# G1000_Pan_Range.net
KiCad netlist of a schematic drawn in EasyEDA
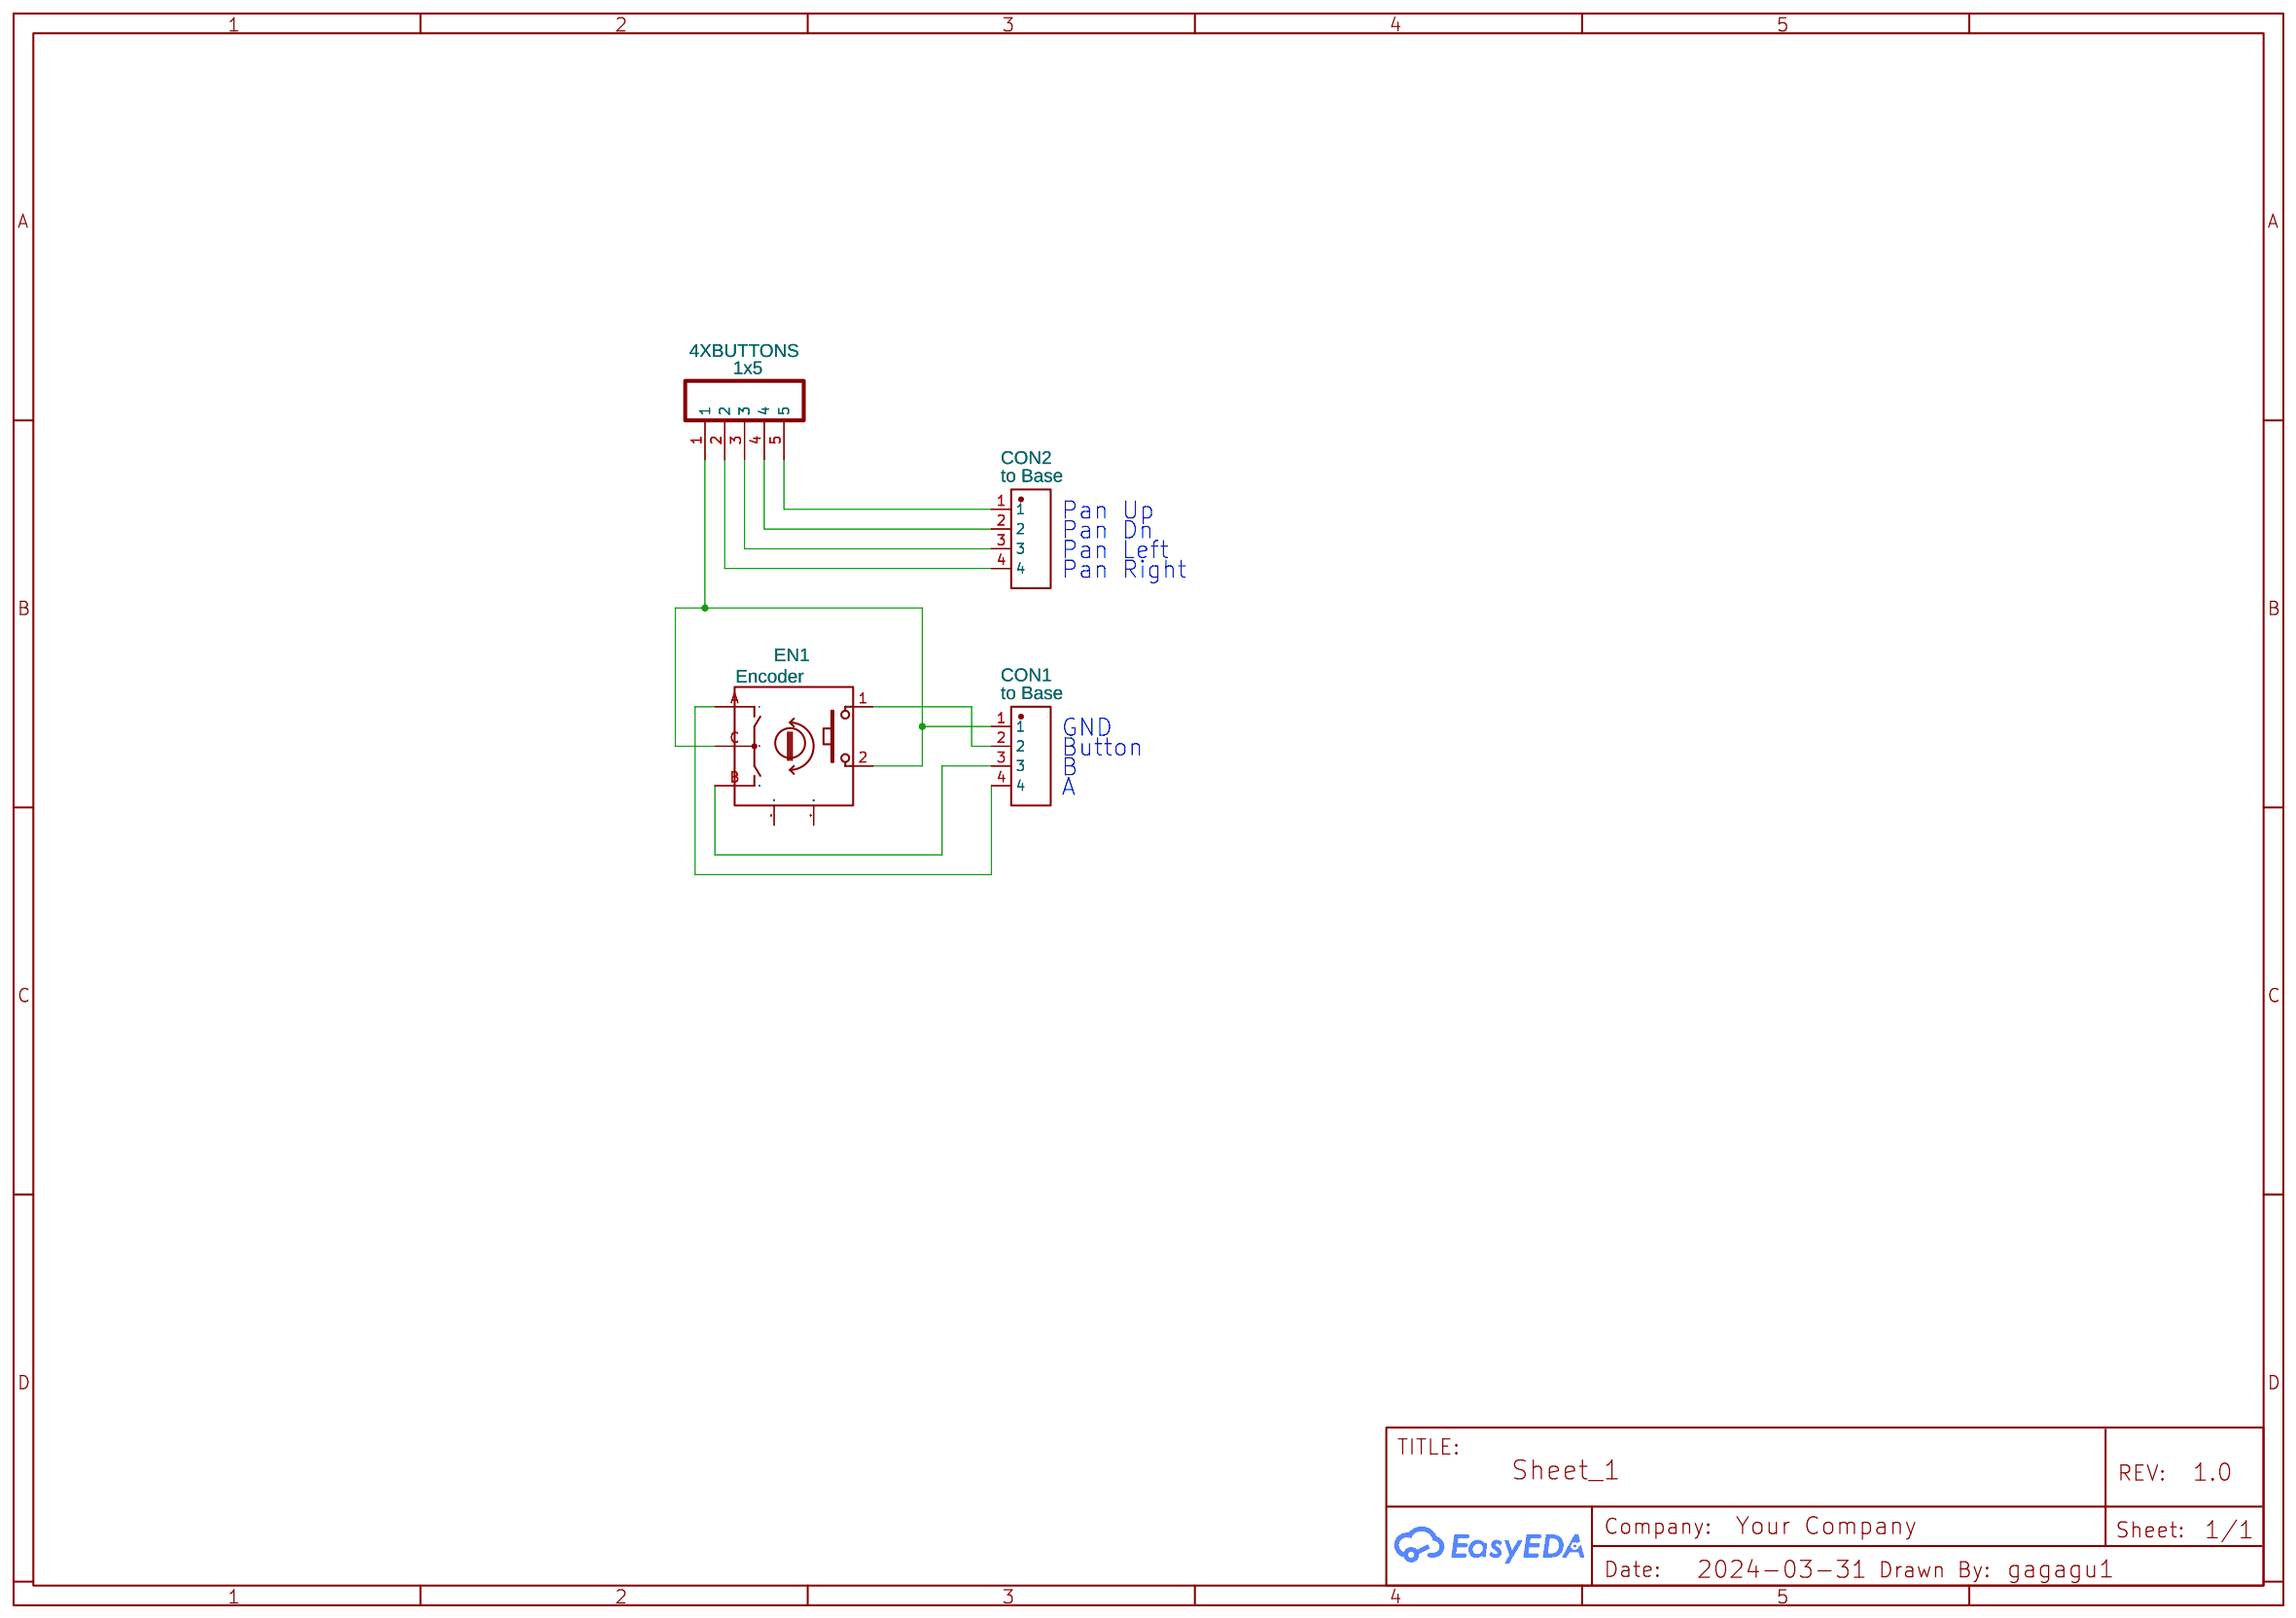
[diagram p0: schematic sheet]

(export (version "E")
  (design (tool "Eeschema 10.0.6"))
  (components
    (comp (ref "4XBUTTONS") (value "1x5") (libsource (lib "") (part "1x5")))
    (comp (ref "CON1")
      (value "to Base")
      (fields (field (name "Manufacturer Part") "XH-4A绿色") (field (name "Manufacturer") "BOOMELE(博穆精密)"))
      (libsource (lib "") (part "ARUN-CONN-TH_XH-4A"))
    )
    (comp (ref "CON2")
      (value "to Base")
      (fields (field (name "Manufacturer Part") "XH-4A绿色") (field (name "Manufacturer") "BOOMELE(博穆精密)"))
      (libsource (lib "") (part "ARUN-CONN-TH_XH-4A"))
    )
    (comp (ref "EN1")
      (value "Encoder")
      (fields (field (name "Manufacturer Part") "PEC11R-4015F-S0024") (field (name "Manufacturer") "BOURNS"))
      (libsource (lib "") (part "PEC11R-4015F-S0024"))
    )
  )
  (nets
    (net (code "1") (name "Net-(4XBUTTONS-Pad1)") (class "Default")
      (node (ref "4XBUTTONS") (pin "1") (pinfunction "1_1") (pintype "unspecified"))
      (node (ref "CON1") (pin "1") (pinfunction "1_1") (pintype "unspecified"))
      (node (ref "EN1") (pin "2") (pinfunction "2_2") (pintype "unspecified"))
      (node (ref "EN1") (pin "C") (pinfunction "C_C") (pintype "unspecified"))
    )
    (net (code "2") (name "Net-(4XBUTTONS-Pad2)") (class "Default")
      (node (ref "4XBUTTONS") (pin "2") (pinfunction "2_2") (pintype "unspecified"))
      (node (ref "CON2") (pin "4") (pinfunction "4_4") (pintype "unspecified"))
    )
    (net (code "3") (name "Net-(4XBUTTONS-Pad3)") (class "Default")
      (node (ref "4XBUTTONS") (pin "3") (pinfunction "3_3") (pintype "unspecified"))
      (node (ref "CON2") (pin "3") (pinfunction "3_3") (pintype "unspecified"))
    )
    (net (code "4") (name "Net-(4XBUTTONS-Pad4)") (class "Default")
      (node (ref "4XBUTTONS") (pin "4") (pinfunction "4_4") (pintype "unspecified"))
      (node (ref "CON2") (pin "2") (pinfunction "2_2") (pintype "unspecified"))
    )
    (net (code "5") (name "Net-(4XBUTTONS-Pad5)") (class "Default")
      (node (ref "4XBUTTONS") (pin "5") (pinfunction "5_5") (pintype "unspecified"))
      (node (ref "CON2") (pin "1") (pinfunction "1_1") (pintype "unspecified"))
    )
    (net (code "6") (name "Net-(CON1-Pad2)") (class "Default")
      (node (ref "CON1") (pin "2") (pinfunction "2_2") (pintype "unspecified"))
      (node (ref "EN1") (pin "1") (pinfunction "1_1") (pintype "unspecified"))
    )
    (net (code "7") (name "Net-(CON1-Pad3)") (class "Default")
      (node (ref "CON1") (pin "3") (pinfunction "3_3") (pintype "unspecified"))
      (node (ref "EN1") (pin "B") (pinfunction "B_B") (pintype "unspecified"))
    )
    (net (code "8") (name "Net-(CON1-Pad4)") (class "Default")
      (node (ref "CON1") (pin "4") (pinfunction "4_4") (pintype "unspecified"))
      (node (ref "EN1") (pin "A") (pinfunction "A_A") (pintype "unspecified"))
    )
    (net (code "9") (name "unconnected-(EN1-PadMT1)") (class "Default")
      (node (ref "EN1") (pin "MT1") (pinfunction "MT1_MT1") (pintype "unspecified"))
    )
    (net (code "10") (name "unconnected-(EN1-PadMT2)") (class "Default")
      (node (ref "EN1") (pin "MT2") (pinfunction "MT2_MT2") (pintype "unspecified"))
    )
  )
)
